# nRF24L01_ESP.net
KiCad netlist of a schematic drawn in EAGLE
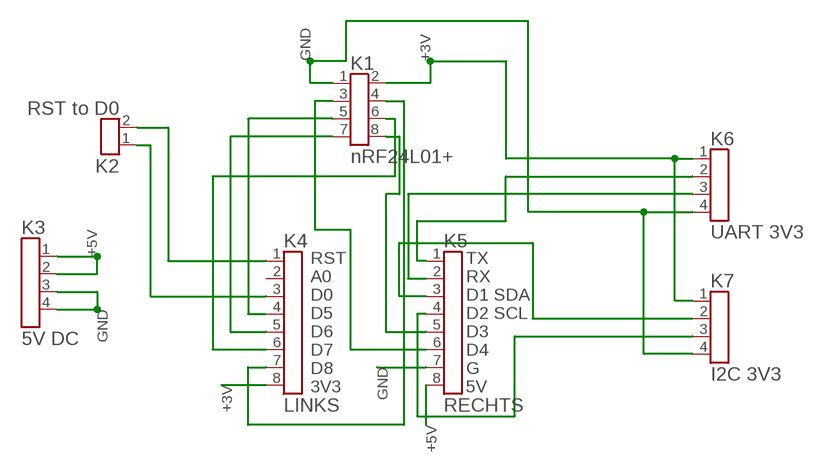
[diagram p0: schematic, sheet 1]

(export (version "E")
  (design (tool "Eeschema 10.0.6"))
  (components
    (comp (ref "K1")
      (value "nRF24L01+")
      (footprint "eagle-import:STIFTLEISTE_2X04_G_2,54_0")
      (libsource (lib "eagle-import") (part "STIFTLEISTE_2X04_G_2,54_0"))
    )
    (comp (ref "K2")
      (value "RST to D0")
      (footprint "eagle-import:STIFTLEISTE_1X02_G_2,54_10")
      (libsource (lib "eagle-import") (part "STIFTLEISTE_1X02_G_2,54_10"))
    )
    (comp (ref "K3")
      (value "5V DC")
      (footprint "eagle-import:KLEMME4_3")
      (libsource (lib "eagle-import") (part "KLEMME4POL_3"))
    )
    (comp (ref "K4")
      (value "LINKS")
      (footprint "eagle-import:STIFTLEISTE_1X08_G_2,54_4")
      (libsource (lib "eagle-import") (part "STIFTLEISTE_1X08_G_2,54_4"))
    )
    (comp (ref "K5")
      (value "RECHTS")
      (footprint "eagle-import:STIFTLEISTE_1X08_G_2,54_5")
      (libsource (lib "eagle-import") (part "STIFTLEISTE_1X08_G_2,54_5"))
    )
    (comp (ref "K6")
      (value "UART 3V3")
      (footprint "eagle-import:STIFTLEISTE_1X04_G_2,54_11")
      (libsource (lib "eagle-import") (part "STIFTLEISTE_1X04_G_2,54_11"))
    )
    (comp (ref "K7")
      (value "I2C 3V3")
      (footprint "eagle-import:STIFTLEISTE_1X04_G_2,54_13")
      (libsource (lib "eagle-import") (part "STIFTLEISTE_1X04_G_2,54_13"))
    )
  )
  (nets
    (net (code "1") (name "/+3V") (class "Default")
      (node (ref "K1") (pin "2") (pinfunction "2_2") (pintype "passive"))
      (node (ref "K4") (pin "8") (pinfunction "8_8") (pintype "passive"))
      (node (ref "K6") (pin "1") (pinfunction "1_1") (pintype "passive"))
      (node (ref "K7") (pin "1") (pinfunction "1_1") (pintype "passive"))
    )
    (net (code "2") (name "/+5V") (class "Default")
      (node (ref "K3") (pin "1") (pinfunction "1_1") (pintype "passive"))
      (node (ref "K3") (pin "2") (pinfunction "2_2") (pintype "passive"))
      (node (ref "K5") (pin "8") (pinfunction "8_8") (pintype "passive"))
    )
    (net (code "3") (name "/GND") (class "Default")
      (node (ref "K1") (pin "1") (pinfunction "1_1") (pintype "passive"))
      (node (ref "K3") (pin "3") (pinfunction "3_3") (pintype "passive"))
      (node (ref "K3") (pin "4") (pinfunction "4_4") (pintype "passive"))
      (node (ref "K5") (pin "7") (pinfunction "7_7") (pintype "passive"))
      (node (ref "K6") (pin "4") (pinfunction "4_4") (pintype "passive"))
      (node (ref "K7") (pin "4") (pinfunction "4_4") (pintype "passive"))
    )
    (net (code "4") (name "Net-(K1-Pad3)") (class "Default")
      (node (ref "K1") (pin "3") (pinfunction "3_3") (pintype "passive"))
      (node (ref "K5") (pin "6") (pinfunction "6_6") (pintype "passive"))
    )
    (net (code "5") (name "Net-(K1-Pad4)") (class "Default")
      (node (ref "K1") (pin "4") (pinfunction "4_4") (pintype "passive"))
      (node (ref "K4") (pin "7") (pinfunction "7_7") (pintype "passive"))
    )
    (net (code "6") (name "Net-(K1-Pad5)") (class "Default")
      (node (ref "K1") (pin "5") (pinfunction "5_5") (pintype "passive"))
      (node (ref "K4") (pin "4") (pinfunction "4_4") (pintype "passive"))
    )
    (net (code "7") (name "Net-(K1-Pad6)") (class "Default")
      (node (ref "K1") (pin "6") (pinfunction "6_6") (pintype "passive"))
      (node (ref "K4") (pin "6") (pinfunction "6_6") (pintype "passive"))
    )
    (net (code "8") (name "Net-(K1-Pad7)") (class "Default")
      (node (ref "K1") (pin "7") (pinfunction "7_7") (pintype "passive"))
      (node (ref "K4") (pin "5") (pinfunction "5_5") (pintype "passive"))
    )
    (net (code "9") (name "Net-(K1-Pad8)") (class "Default")
      (node (ref "K1") (pin "8") (pinfunction "8_8") (pintype "passive"))
      (node (ref "K5") (pin "5") (pinfunction "5_5") (pintype "passive"))
    )
    (net (code "10") (name "Net-(K2-Pad1)") (class "Default")
      (node (ref "K2") (pin "1") (pinfunction "1_1") (pintype "passive"))
      (node (ref "K4") (pin "3") (pinfunction "3_3") (pintype "passive"))
    )
    (net (code "11") (name "Net-(K2-Pad2)") (class "Default")
      (node (ref "K2") (pin "2") (pinfunction "2_2") (pintype "passive"))
      (node (ref "K4") (pin "1") (pinfunction "1_1") (pintype "passive"))
    )
    (net (code "12") (name "Net-(K5-Pad1)") (class "Default")
      (node (ref "K5") (pin "1") (pinfunction "1_1") (pintype "passive"))
      (node (ref "K6") (pin "2") (pinfunction "2_2") (pintype "passive"))
    )
    (net (code "13") (name "Net-(K5-Pad2)") (class "Default")
      (node (ref "K5") (pin "2") (pinfunction "2_2") (pintype "passive"))
      (node (ref "K6") (pin "3") (pinfunction "3_3") (pintype "passive"))
    )
    (net (code "14") (name "Net-(K5-Pad3)") (class "Default")
      (node (ref "K5") (pin "3") (pinfunction "3_3") (pintype "passive"))
      (node (ref "K7") (pin "2") (pinfunction "2_2") (pintype "passive"))
    )
    (net (code "15") (name "Net-(K5-Pad4)") (class "Default")
      (node (ref "K5") (pin "4") (pinfunction "4_4") (pintype "passive"))
      (node (ref "K7") (pin "3") (pinfunction "3_3") (pintype "passive"))
    )
    (net (code "16") (name "unconnected-(K4-Pad2)") (class "Default")
      (node (ref "K4") (pin "2") (pinfunction "2_2") (pintype "passive"))
    )
  )
)
